# 4_SurvBot_RCU_Bluetooth.net
KiCad netlist of a schematic drawn in Altium Designer
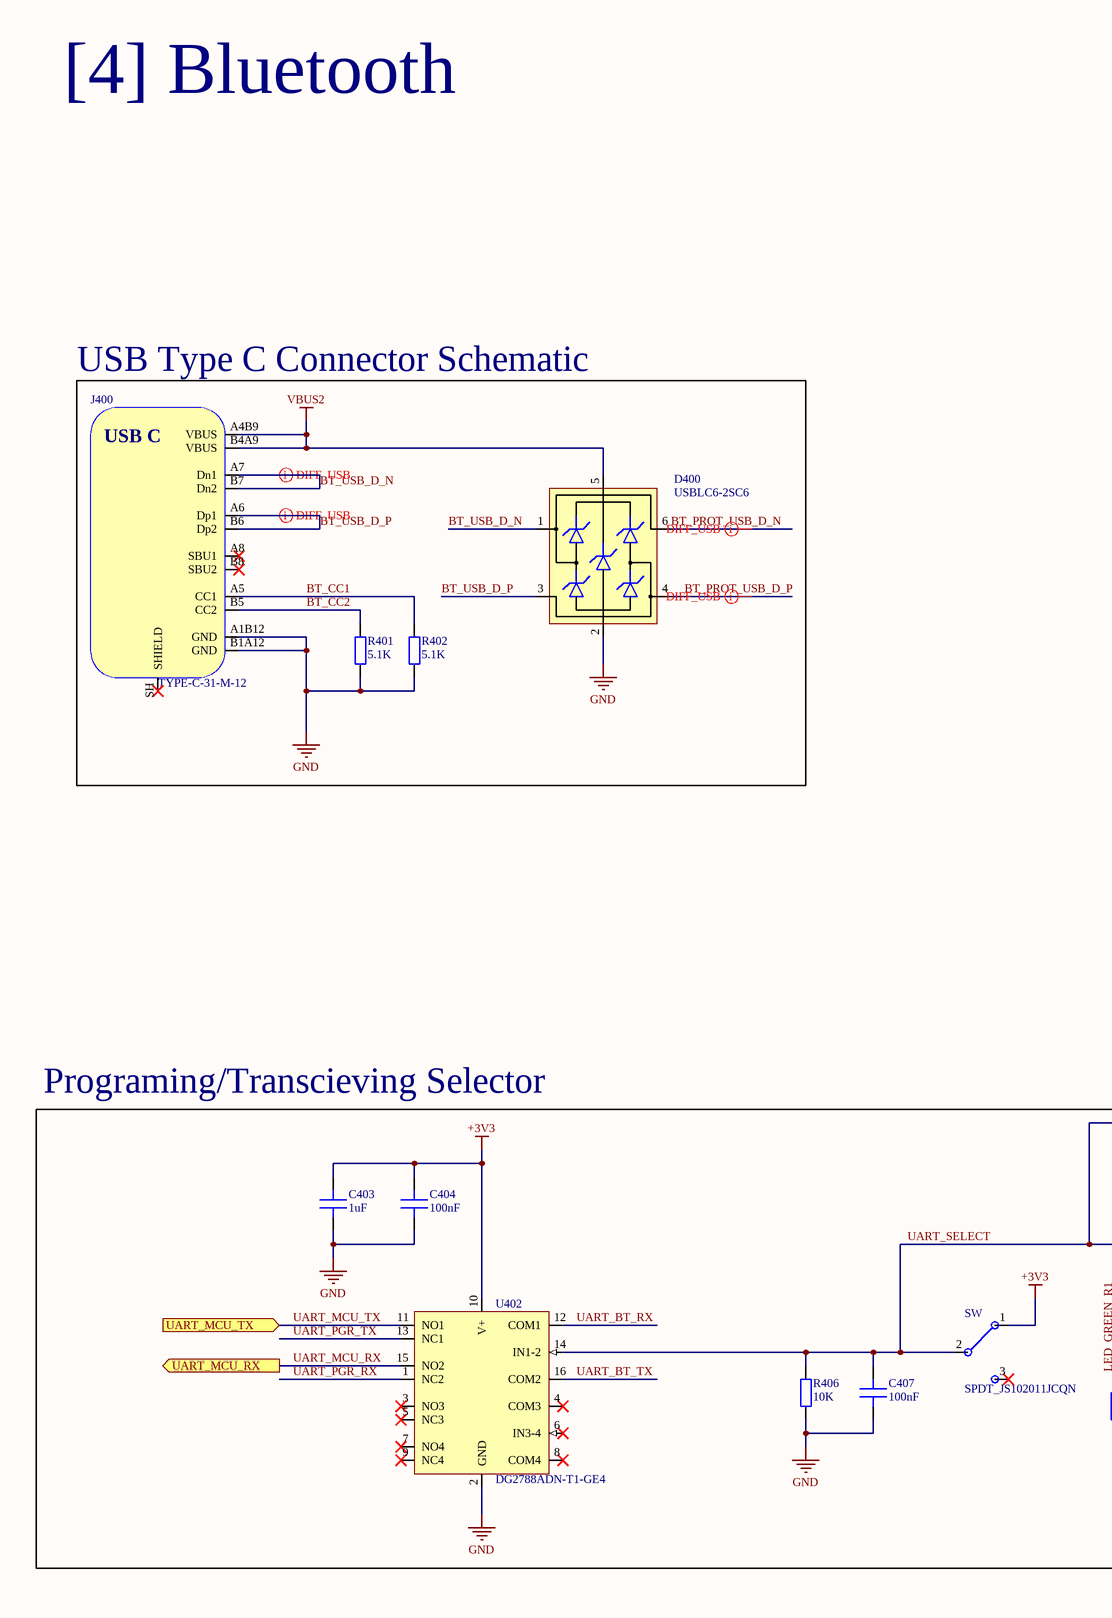
[diagram p0: 4_SurvBot_RCU_Bluetooth.SchDoc, left]
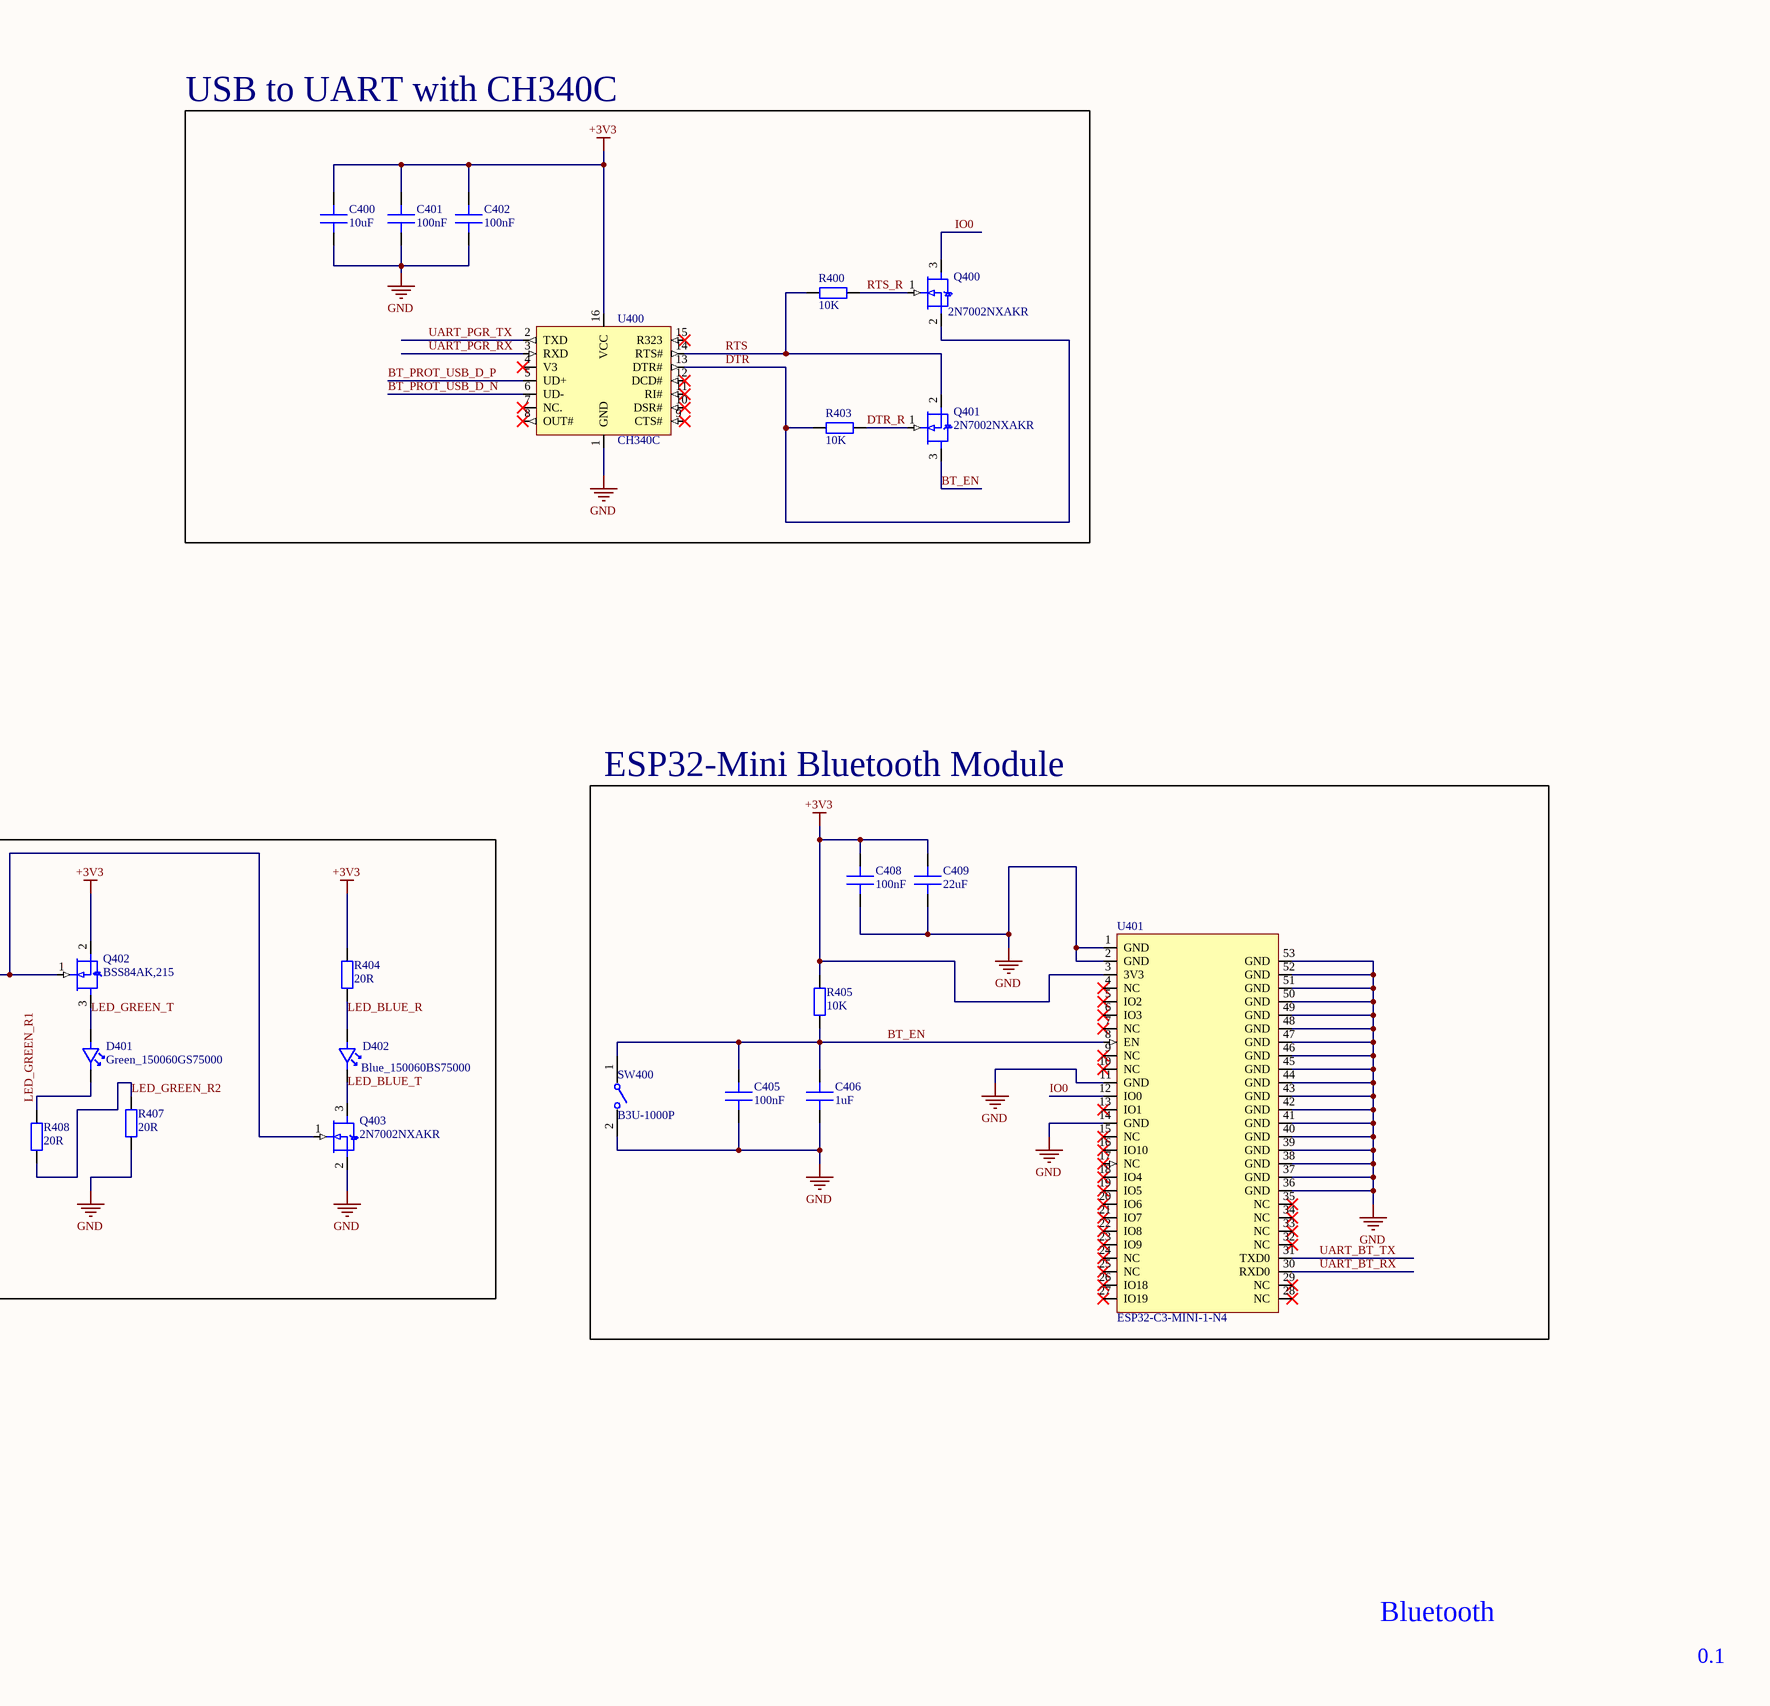
[diagram p1: 4_SurvBot_RCU_Bluetooth.SchDoc, right]

(export (version "E")
  (design (tool "Eeschema 10.0.6"))
  (components
    (comp (ref "C400")
      (value "10uF")
      (footprint "CAP_0603")
      (description "10 µF ±20% 10V Ceramic Capacitor X5R 0603 (1608 Metric)")
      (fields
        (field (name "MANUFACTURER") "Murata Electronics")
        (field (name "MANUFACTURER PART #") "GRM188R61A106ME69D")
      )
      (libsource (lib "GhaniLibrary") (part "CAP_10uF-10V-20%-0603"))
    )
    (comp (ref "C401")
      (value "100nF")
      (footprint "CAP_0603")
      (description "0.1 µF ±10% 50V Ceramic Capacitor X7R 0603 (1608 Metric)")
      (fields (field (name "MANUFACTURER") "KEMET") (field (name "MANUFACTURER PART #") "C0603C104K5RACAUTO"))
      (libsource (lib "GhaniLibrary") (part "CAP_100nF-50V-10%-0603"))
    )
    (comp (ref "C402")
      (value "100nF")
      (footprint "CAP_0603")
      (description "0.1 µF ±10% 50V Ceramic Capacitor X7R 0603 (1608 Metric)")
      (fields (field (name "MANUFACTURER") "KEMET") (field (name "MANUFACTURER PART #") "C0603C104K5RACAUTO"))
      (libsource (lib "GhaniLibrary") (part "CAP_100nF-50V-10%-0603"))
    )
    (comp (ref "C403")
      (value "1uF")
      (footprint "CAP_0603")
      (description "1 µF ±10% 16V Ceramic Capacitor X7R 0603 (1608 Metric)")
      (fields (field (name "MANUFACTURER") "YAGEO") (field (name "MANUFACTURER PART #") "CC0603KRX7R7BB105"))
      (libsource (lib "GhaniLibrary") (part "CAP_1uF-16V-10%-0603"))
    )
    (comp (ref "C404")
      (value "100nF")
      (footprint "CAP_0603")
      (description "0.1 µF ±10% 50V Ceramic Capacitor X7R 0603 (1608 Metric)")
      (fields (field (name "MANUFACTURER") "KEMET") (field (name "MANUFACTURER PART #") "C0603C104K5RACAUTO"))
      (libsource (lib "GhaniLibrary") (part "CAP_100nF-50V-10%-0603"))
    )
    (comp (ref "C405")
      (value "100nF")
      (footprint "CAP_0603")
      (description "0.1 µF ±10% 50V Ceramic Capacitor X7R 0603 (1608 Metric)")
      (fields (field (name "MANUFACTURER") "KEMET") (field (name "MANUFACTURER PART #") "C0603C104K5RACAUTO"))
      (libsource (lib "GhaniLibrary") (part "CAP_100nF-50V-10%-0603"))
    )
    (comp (ref "C406")
      (value "1uF")
      (footprint "CAP_0603")
      (description "1 µF ±10% 16V Ceramic Capacitor X7R 0603 (1608 Metric)")
      (fields (field (name "MANUFACTURER") "YAGEO") (field (name "MANUFACTURER PART #") "CC0603KRX7R7BB105"))
      (libsource (lib "GhaniLibrary") (part "CAP_1uF-16V-10%-0603"))
    )
    (comp (ref "C407")
      (value "100nF")
      (footprint "CAP_0603")
      (description "0.1 µF ±10% 50V Ceramic Capacitor X7R 0603 (1608 Metric)")
      (fields (field (name "MANUFACTURER") "KEMET") (field (name "MANUFACTURER PART #") "C0603C104K5RACAUTO"))
      (libsource (lib "GhaniLibrary") (part "CAP_100nF-50V-10%-0603"))
    )
    (comp (ref "C408")
      (value "100nF")
      (footprint "CAP_0603")
      (description "0.1 µF ±10% 50V Ceramic Capacitor X7R 0603 (1608 Metric)")
      (fields (field (name "MANUFACTURER") "KEMET") (field (name "MANUFACTURER PART #") "C0603C104K5RACAUTO"))
      (libsource (lib "GhaniLibrary") (part "CAP_100nF-50V-10%-0603"))
    )
    (comp (ref "C409")
      (value "22uF")
      (footprint "CAP_0603")
      (description "22 µF ±20% 10V Ceramic Capacitor X5R 0603 (1608 Metric)")
      (fields
        (field (name "MANUFACTURER") "Samsung Electro-Mechanics")
        (field (name "MANUFACTURER PART #") "CL10A226MP8NUNE")
      )
      (libsource (lib "GhaniLibrary") (part "CAP_22uF-10V-20%-0603"))
    )
    (comp (ref "D400")
      (value "USBLC6-2SC6")
      (footprint "SOT-23-6")
      (description "Low-Capacitance ESD Protection USB")
      (fields (field (name "MANUFACTURER") "STMicroelectronics"))
      (libsource (lib "Schematic-Lib-PhilsLab") (part "USBLC6-2SC6"))
    )
    (comp (ref "D401")
      (value "Green_150060GS75000")
      (footprint "LED_0603")
      (description "Green 520nm LED Indication - Discrete 3.2V 0603 (1608 Metric)")
      (fields
        (field (name "MANUFACTURER") "Wurth Elektronik")
        (field (name "MANUFACTURER PART #") "150060GS75000")
      )
      (libsource (lib "GhaniLibrary") (part "LED_Green-0603"))
    )
    (comp (ref "D402")
      (value "Blue_150060BS75000")
      (footprint "LED_0603")
      (description "Blue 470nm LED Indication - Discrete 3.2V 0603 (1608 Metric)")
      (fields
        (field (name "MANUFACTURER") "Wurth Elektronik")
        (field (name "MANUFACTURER PART #") "150060BS75000")
      )
      (libsource (lib "GhaniLibrary") (part "LED_Blue_0603"))
    )
    (comp (ref "J400")
      (value "TYPE-C-31-M-12")
      (footprint "USB4105-GF-A-060")
      (description "5A 1 16P Female Type-C SMD USB Connectors ROHS")
      (fields (field (name "MANUFACTURER") "Korean Hroparts Elec"))
      (libsource (lib "Schematic-Lib-PhilsLab") (part "USB4105-GF-A-060_1"))
    )
    (comp (ref "Q400")
      (value "2N7002NXAKR")
      (footprint "SOT23-3")
      (description "N-Channel 60 V 190mA (Ta), 300mA (Tc) 265mW (Ta), 1.33W (Tc) Surface Mount TO-236AB")
      (fields (field (name "MANUFACTURER") "Nexperia"))
      (libsource (lib "GhaniLibrary") (part "MOSFET-N_60V-190mA-SOT23-3"))
    )
    (comp (ref "Q401")
      (value "2N7002NXAKR")
      (footprint "SOT23-3")
      (description "N-Channel 60 V 190mA (Ta), 300mA (Tc) 265mW (Ta), 1.33W (Tc) Surface Mount TO-236AB")
      (fields (field (name "MANUFACTURER") "Nexperia"))
      (libsource (lib "GhaniLibrary") (part "MOSFET-N_60V-190mA-SOT23-3"))
    )
    (comp (ref "Q402")
      (value "BSS84AK,215")
      (footprint "SOT23-3")
      (description "P-Channel 50 V 180mA (Ta) 350mW (Ta), 1.14W (Tc) Surface Mount TO-236AB")
      (fields (field (name "MANUFACTURER") "Nexperia"))
      (libsource (lib "GhaniLibrary") (part "MOSFET-P_50V-180mA-SOT23-3"))
    )
    (comp (ref "Q403")
      (value "2N7002NXAKR")
      (footprint "SOT23-3")
      (description "N-Channel 60 V 190mA (Ta), 300mA (Tc) 265mW (Ta), 1.33W (Tc) Surface Mount TO-236AB")
      (fields (field (name "MANUFACTURER") "Nexperia"))
      (libsource (lib "GhaniLibrary") (part "MOSFET-N_60V-190mA-SOT23-3"))
    )
    (comp (ref "R400")
      (value "10K")
      (footprint "RES_0603")
      (description "10 kOhms ±1% 0.1W, 1/10W Chip Resistor 0603 (1608 Metric) Moisture Resistant Thick Film")
      (fields (field (name "MANUFACTURER") "YAGEO") (field (name "MANUFACTURER PART #") "RC0603FR-0710KL"))
      (libsource (lib "GhaniLibrary") (part "RES_10K-100mW-1%-0603"))
    )
    (comp (ref "R401")
      (value "5.1K")
      (footprint "RES_0603")
      (description "5.1 kOhms ±1% 0.1W, 1/10W Chip Resistor 0603 (1608 Metric) Moisture Resistant Thick Film")
      (fields (field (name "MANUFACTURER") "YAGEO") (field (name "MANUFACTURER PART #") "RC0603FR-075K1L"))
      (libsource (lib "GhaniLibrary") (part "RES_5.1K-100mW-1%-0603"))
    )
    (comp (ref "R402")
      (value "5.1K")
      (footprint "RES_0603")
      (description "5.1 kOhms ±1% 0.1W, 1/10W Chip Resistor 0603 (1608 Metric) Moisture Resistant Thick Film")
      (fields (field (name "MANUFACTURER") "YAGEO") (field (name "MANUFACTURER PART #") "RC0603FR-075K1L"))
      (libsource (lib "GhaniLibrary") (part "RES_5.1K-100mW-1%-0603"))
    )
    (comp (ref "R403")
      (value "10K")
      (footprint "RES_0603")
      (description "10 kOhms ±1% 0.1W, 1/10W Chip Resistor 0603 (1608 Metric) Moisture Resistant Thick Film")
      (fields (field (name "MANUFACTURER") "YAGEO") (field (name "MANUFACTURER PART #") "RC0603FR-0710KL"))
      (libsource (lib "GhaniLibrary") (part "RES_10K-100mW-1%-0603"))
    )
    (comp (ref "R404")
      (value "20R")
      (footprint "RES_0603")
      (description "20 Ohms ±1% 0.1W, 1/10W Chip Resistor 0603 (1608 Metric) Moisture Resistant Thick Film")
      (fields (field (name "MANUFACTURER") "YAGEO") (field (name "MANUFACTURER PART #") "RC0603FR-0720RL"))
      (libsource (lib "GhaniLibrary") (part "RES_20R-100mW-1%-0603"))
    )
    (comp (ref "R405")
      (value "10K")
      (footprint "RES_0603")
      (description "10 kOhms ±1% 0.1W, 1/10W Chip Resistor 0603 (1608 Metric) Moisture Resistant Thick Film")
      (fields (field (name "MANUFACTURER") "YAGEO") (field (name "MANUFACTURER PART #") "RC0603FR-0710KL"))
      (libsource (lib "GhaniLibrary") (part "RES_10K-100mW-1%-0603"))
    )
    (comp (ref "R406")
      (value "10K")
      (footprint "RES_0603")
      (description "10 kOhms ±1% 0.1W, 1/10W Chip Resistor 0603 (1608 Metric) Moisture Resistant Thick Film")
      (fields (field (name "MANUFACTURER") "YAGEO") (field (name "MANUFACTURER PART #") "RC0603FR-0710KL"))
      (libsource (lib "GhaniLibrary") (part "RES_10K-100mW-1%-0603"))
    )
    (comp (ref "R407")
      (value "20R")
      (footprint "RES_0603")
      (description "20 Ohms ±1% 0.1W, 1/10W Chip Resistor 0603 (1608 Metric) Moisture Resistant Thick Film")
      (fields (field (name "MANUFACTURER") "YAGEO") (field (name "MANUFACTURER PART #") "RC0603FR-0720RL"))
      (libsource (lib "GhaniLibrary") (part "RES_20R-100mW-1%-0603"))
    )
    (comp (ref "R408")
      (value "20R")
      (footprint "RES_0603")
      (description "20 Ohms ±1% 0.1W, 1/10W Chip Resistor 0603 (1608 Metric) Moisture Resistant Thick Film")
      (fields (field (name "MANUFACTURER") "YAGEO") (field (name "MANUFACTURER PART #") "RC0603FR-0720RL"))
      (libsource (lib "GhaniLibrary") (part "RES_20R-100mW-1%-0603"))
    )
    (comp (ref "SW")
      (value "SPDT_JS102011JCQN")
      (footprint "SPDT_Slide-JS102011JCQN")
      (description "Slide Switch SPDT Surface Mount")
      (fields (field (name "MANUFACTURER") "C&K") (field (name "MANUFACTURER PART #") "JS102011JCQN"))
      (libsource (lib "GhaniLibrary") (part "SW_SPDT_JS102011JCQN"))
    )
    (comp (ref "SW400")
      (value "B3U-1000P")
      (footprint "FP-B3U-1000P-MFG")
      (description "SWITCH TACTILE SPST-NO 0.05A 12V")
      (fields (field (name "MANUFACTURER") "Omron Electronics"))
      (libsource (lib "Altium Content Vault") (part "ae622034201233ca1abcedc05908f33"))
    )
    (comp (ref "U400")
      (value "CH340C")
      (footprint "SOP-16")
      (description "2Mbps Transceiver USB 2.0 SOP-16 USB Converters ROHS")
      (fields (field (name "MANUFACTURER") "WCH(Jiangsu Qin Heng)"))
      (libsource (lib "GhaniLibrary") (part "CH340C-SOP-16_USB_Converter"))
    )
    (comp (ref "U401")
      (value "ESP32-C3-MINI-1-N4")
      (footprint "ESP32­C3­MINI­1")
      (fields (field (name "MANUFACTURER") "Espressif Systems"))
      (libsource (lib "GhaniLibrary") (part "MCU_ESP32-C3-MINI-1-N4"))
    )
    (comp (ref "U402")
      (value "DG2788ADN-T1-GE4")
      (footprint "UQFN-16-DG2788ADN-T1-GE4")
      (description "2 Circuit IC Switch 2:1 500mOhm 16-miniQFN (1.8x2.6)")
      (fields (field (name "MANUFACTURER") "Vishay Intertech"))
      (libsource (lib "GhaniLibrary") (part "IC_DG2788ADN-T1-GE4"))
    )
  )
  (nets
    (net (code "1") (name "+3V3") (class "Default")
      (node (ref "C400") (pin "2") (pinfunction "0_2") (pintype "passive"))
      (node (ref "C401") (pin "2") (pinfunction "0_2") (pintype "passive"))
      (node (ref "C402") (pin "2") (pinfunction "0_2") (pintype "passive"))
      (node (ref "C403") (pin "2") (pinfunction "0_2") (pintype "passive"))
      (node (ref "C404") (pin "2") (pinfunction "0_2") (pintype "passive"))
      (node (ref "C408") (pin "2") (pinfunction "0_2") (pintype "passive"))
      (node (ref "C409") (pin "2") (pinfunction "0_2") (pintype "passive"))
      (node (ref "Q402") (pin "2") (pinfunction "S_2") (pintype "passive"))
      (node (ref "R404") (pin "1") (pinfunction "1_1") (pintype "passive"))
      (node (ref "R405") (pin "2") (pinfunction "2_2") (pintype "passive"))
      (node (ref "SW") (pin "1") (pintype "passive"))
      (node (ref "U400") (pin "16") (pinfunction "VCC_16") (pintype "power_in"))
      (node (ref "U401") (pin "3") (pinfunction "3V3_3") (pintype "power_in"))
      (node (ref "U402") (pin "10") (pinfunction "V+_10") (pintype "power_in"))
    )
    (net (code "2") (name "/BT_CC1") (class "Default")
      (node (ref "J400") (pin "A5") (pinfunction "CC1_A5") (pintype "passive"))
      (node (ref "R402") (pin "2") (pinfunction "2_2") (pintype "passive"))
    )
    (net (code "3") (name "/BT_CC2") (class "Default")
      (node (ref "J400") (pin "B5") (pinfunction "CC2_B5") (pintype "passive"))
      (node (ref "R401") (pin "2") (pinfunction "2_2") (pintype "passive"))
    )
    (net (code "4") (name "/BT_EN") (class "Default")
      (node (ref "C405") (pin "2") (pinfunction "0_2") (pintype "passive"))
      (node (ref "C406") (pin "2") (pinfunction "0_2") (pintype "passive"))
      (node (ref "Q401") (pin "3") (pinfunction "D_3") (pintype "passive"))
      (node (ref "R405") (pin "1") (pinfunction "1_1") (pintype "passive"))
      (node (ref "SW400") (pin "1") (pinfunction "1_1") (pintype "passive"))
      (node (ref "U401") (pin "8") (pinfunction "EN_8") (pintype "input"))
    )
    (net (code "5") (name "/BT_PROT_USB_D_N") (class "Default")
      (node (ref "D400") (pin "6") (pinfunction "IO1_6") (pintype "bidirectional"))
      (node (ref "U400") (pin "6") (pinfunction "UD-_6") (pintype "bidirectional"))
    )
    (net (code "6") (name "/BT_PROT_USB_D_P") (class "Default")
      (node (ref "D400") (pin "4") (pinfunction "IO2_4") (pintype "bidirectional"))
      (node (ref "U400") (pin "5") (pinfunction "UD+_5") (pintype "bidirectional"))
    )
    (net (code "7") (name "/BT_USB_D_N") (class "Default")
      (node (ref "D400") (pin "1") (pinfunction "IO1_1") (pintype "bidirectional"))
      (node (ref "J400") (pin "A7") (pinfunction "Dn1_A7") (pintype "passive"))
      (node (ref "J400") (pin "B7") (pinfunction "Dn2_B7") (pintype "passive"))
    )
    (net (code "8") (name "/BT_USB_D_P") (class "Default")
      (node (ref "D400") (pin "3") (pinfunction "IO2_3") (pintype "bidirectional"))
      (node (ref "J400") (pin "A6") (pinfunction "Dp1_A6") (pintype "passive"))
      (node (ref "J400") (pin "B6") (pinfunction "Dp2_B6") (pintype "passive"))
    )
    (net (code "9") (name "/DTR") (class "Default")
      (node (ref "Q400") (pin "2") (pinfunction "S_2") (pintype "passive"))
      (node (ref "R403") (pin "1") (pinfunction "1_1") (pintype "passive"))
      (node (ref "U400") (pin "13") (pinfunction "DTR#_13") (pintype "output"))
    )
    (net (code "10") (name "/DTR_R") (class "Default")
      (node (ref "Q401") (pin "1") (pinfunction "G_1") (pintype "input"))
      (node (ref "R403") (pin "2") (pinfunction "2_2") (pintype "passive"))
    )
    (net (code "11") (name "/IO0") (class "Default")
      (node (ref "Q400") (pin "3") (pinfunction "D_3") (pintype "passive"))
      (node (ref "U401") (pin "12") (pinfunction "IO0_12") (pintype "bidirectional"))
    )
    (net (code "12") (name "/LED_BLUE_R") (class "Default")
      (node (ref "D402") (pin "2") (pinfunction "2_2") (pintype "passive"))
      (node (ref "R404") (pin "2") (pinfunction "2_2") (pintype "passive"))
    )
    (net (code "13") (name "/LED_BLUE_T") (class "Default")
      (node (ref "D402") (pin "1") (pinfunction "1_1") (pintype "passive"))
      (node (ref "Q403") (pin "3") (pinfunction "D_3") (pintype "passive"))
    )
    (net (code "14") (name "/LED_GREEN_R1") (class "Default")
      (node (ref "D401") (pin "1") (pinfunction "1_1") (pintype "passive"))
      (node (ref "R408") (pin "1") (pinfunction "1_1") (pintype "passive"))
    )
    (net (code "15") (name "/LED_GREEN_R2") (class "Default")
      (node (ref "R407") (pin "2") (pinfunction "2_2") (pintype "passive"))
      (node (ref "R408") (pin "2") (pinfunction "2_2") (pintype "passive"))
    )
    (net (code "16") (name "/LED_GREEN_T") (class "Default")
      (node (ref "D401") (pin "2") (pinfunction "2_2") (pintype "passive"))
      (node (ref "Q402") (pin "3") (pinfunction "D_3") (pintype "passive"))
    )
    (net (code "17") (name "/RTS") (class "Default")
      (node (ref "Q401") (pin "2") (pinfunction "S_2") (pintype "passive"))
      (node (ref "R400") (pin "1") (pinfunction "1_1") (pintype "passive"))
      (node (ref "U400") (pin "14") (pinfunction "RTS#_14") (pintype "output"))
    )
    (net (code "18") (name "/RTS_R") (class "Default")
      (node (ref "Q400") (pin "1") (pinfunction "G_1") (pintype "input"))
      (node (ref "R400") (pin "2") (pinfunction "2_2") (pintype "passive"))
    )
    (net (code "19") (name "/UART_BT_RX") (class "Default")
      (node (ref "U401") (pin "30") (pinfunction "RXD0_30") (pintype "bidirectional"))
      (node (ref "U402") (pin "12") (pinfunction "COM1_12") (pintype "bidirectional"))
    )
    (net (code "20") (name "/UART_BT_TX") (class "Default")
      (node (ref "U401") (pin "31") (pinfunction "TXD0_31") (pintype "bidirectional"))
      (node (ref "U402") (pin "16") (pinfunction "COM2_16") (pintype "bidirectional"))
    )
    (net (code "21") (name "/UART_MCU_RX") (class "Default")
      (node (ref "U402") (pin "15") (pinfunction "NO2_15") (pintype "bidirectional"))
    )
    (net (code "22") (name "/UART_MCU_TX") (class "Default")
      (node (ref "U402") (pin "11") (pinfunction "NO1_11") (pintype "bidirectional"))
    )
    (net (code "23") (name "/UART_PGR_RX") (class "Default")
      (node (ref "U400") (pin "3") (pinfunction "RXD_3") (pintype "input"))
      (node (ref "U402") (pin "1") (pinfunction "NC2_1") (pintype "bidirectional"))
    )
    (net (code "24") (name "/UART_PGR_TX") (class "Default")
      (node (ref "U400") (pin "2") (pinfunction "TXD_2") (pintype "output"))
      (node (ref "U402") (pin "13") (pinfunction "NC1_13") (pintype "bidirectional"))
    )
    (net (code "25") (name "/UART_SELECT") (class "Default")
      (node (ref "C407") (pin "2") (pinfunction "0_2") (pintype "passive"))
      (node (ref "Q402") (pin "1") (pinfunction "G_1") (pintype "input"))
      (node (ref "Q403") (pin "1") (pinfunction "G_1") (pintype "input"))
      (node (ref "R406") (pin "2") (pinfunction "2_2") (pintype "passive"))
      (node (ref "SW") (pin "2") (pintype "passive"))
      (node (ref "U402") (pin "14") (pinfunction "IN1-2_14") (pintype "input"))
    )
    (net (code "26") (name "GND") (class "Default")
      (node (ref "C400") (pin "1") (pinfunction "0_1") (pintype "passive"))
      (node (ref "C401") (pin "1") (pinfunction "0_1") (pintype "passive"))
      (node (ref "C402") (pin "1") (pinfunction "0_1") (pintype "passive"))
      (node (ref "C403") (pin "1") (pinfunction "0_1") (pintype "passive"))
      (node (ref "C404") (pin "1") (pinfunction "0_1") (pintype "passive"))
      (node (ref "C405") (pin "1") (pinfunction "0_1") (pintype "passive"))
      (node (ref "C406") (pin "1") (pinfunction "0_1") (pintype "passive"))
      (node (ref "C407") (pin "1") (pinfunction "0_1") (pintype "passive"))
      (node (ref "C408") (pin "1") (pinfunction "0_1") (pintype "passive"))
      (node (ref "C409") (pin "1") (pinfunction "0_1") (pintype "passive"))
      (node (ref "D400") (pin "2") (pinfunction "GND_2") (pintype "power_in"))
      (node (ref "J400") (pin "A1B12") (pinfunction "GND_A1B12") (pintype "passive"))
      (node (ref "J400") (pin "B1A12") (pinfunction "GND_B1A12") (pintype "passive"))
      (node (ref "Q403") (pin "2") (pinfunction "S_2") (pintype "passive"))
      (node (ref "R401") (pin "1") (pinfunction "1_1") (pintype "passive"))
      (node (ref "R402") (pin "1") (pinfunction "1_1") (pintype "passive"))
      (node (ref "R406") (pin "1") (pinfunction "1_1") (pintype "passive"))
      (node (ref "R407") (pin "1") (pinfunction "1_1") (pintype "passive"))
      (node (ref "SW400") (pin "2") (pinfunction "2_2") (pintype "passive"))
      (node (ref "U400") (pin "1") (pinfunction "GND_1") (pintype "power_in"))
      (node (ref "U401") (pin "1") (pinfunction "GND_1") (pintype "power_in"))
      (node (ref "U401") (pin "11") (pinfunction "GND_11") (pintype "power_in"))
      (node (ref "U401") (pin "14") (pinfunction "GND_14") (pintype "power_in"))
      (node (ref "U401") (pin "2") (pinfunction "GND_2") (pintype "power_in"))
      (node (ref "U401") (pin "36") (pinfunction "GND_36") (pintype "power_in"))
      (node (ref "U401") (pin "37") (pinfunction "GND_37") (pintype "power_in"))
      (node (ref "U401") (pin "38") (pinfunction "GND_38") (pintype "power_in"))
      (node (ref "U401") (pin "39") (pinfunction "GND_39") (pintype "power_in"))
      (node (ref "U401") (pin "40") (pinfunction "GND_40") (pintype "power_in"))
      (node (ref "U401") (pin "41") (pinfunction "GND_41") (pintype "power_in"))
      (node (ref "U401") (pin "42") (pinfunction "GND_42") (pintype "power_in"))
      (node (ref "U401") (pin "43") (pinfunction "GND_43") (pintype "power_in"))
      (node (ref "U401") (pin "44") (pinfunction "GND_44") (pintype "power_in"))
      (node (ref "U401") (pin "45") (pinfunction "GND_45") (pintype "power_in"))
      (node (ref "U401") (pin "46") (pinfunction "GND_46") (pintype "power_in"))
      (node (ref "U401") (pin "47") (pinfunction "GND_47") (pintype "power_in"))
      (node (ref "U401") (pin "48") (pinfunction "GND_48") (pintype "power_in"))
      (node (ref "U401") (pin "49") (pinfunction "GND_49") (pintype "power_in"))
      (node (ref "U401") (pin "50") (pinfunction "GND_50") (pintype "power_in"))
      (node (ref "U401") (pin "51") (pinfunction "GND_51") (pintype "power_in"))
      (node (ref "U401") (pin "52") (pinfunction "GND_52") (pintype "power_in"))
      (node (ref "U401") (pin "53") (pinfunction "GND_53") (pintype "power_in"))
      (node (ref "U402") (pin "2") (pinfunction "GND_2") (pintype "power_in"))
    )
    (net (code "27") (name "VBUS2") (class "Default")
      (node (ref "D400") (pin "5") (pinfunction "VBUS_5") (pintype "power_in"))
      (node (ref "J400") (pin "A4B9") (pinfunction "VBUS_A4B9") (pintype "passive"))
      (node (ref "J400") (pin "B4A9") (pinfunction "VBUS_B4A9") (pintype "passive"))
    )
    (net (code "28") (name "unconnected-(J400-SBU1-PadA8)") (class "Default")
      (node (ref "J400") (pin "A8") (pinfunction "SBU1_A8") (pintype "passive+no_connect"))
    )
    (net (code "29") (name "unconnected-(J400-SBU2-PadB8)") (class "Default")
      (node (ref "J400") (pin "B8") (pinfunction "SBU2_B8") (pintype "passive+no_connect"))
    )
    (net (code "30") (name "unconnected-(J400-SHIELD-PadSH)") (class "Default")
      (node (ref "J400") (pin "SH") (pinfunction "SHIELD_SH") (pintype "passive+no_connect"))
    )
    (net (code "31") (name "unconnected-(SW-Pad3)") (class "Default")
      (node (ref "SW") (pin "3") (pintype "passive+no_connect"))
    )
    (net (code "32") (name "unconnected-(U400-CTS#-Pad9)") (class "Default")
      (node (ref "U400") (pin "9") (pinfunction "CTS#_9") (pintype "input+no_connect"))
    )
    (net (code "33") (name "unconnected-(U400-DCD#-Pad12)") (class "Default")
      (node (ref "U400") (pin "12") (pinfunction "DCD#_12") (pintype "input+no_connect"))
    )
    (net (code "34") (name "unconnected-(U400-DSR#-Pad10)") (class "Default")
      (node (ref "U400") (pin "10") (pinfunction "DSR#_10") (pintype "input+no_connect"))
    )
    (net (code "35") (name "unconnected-(U400-NC.-Pad7)") (class "Default")
      (node (ref "U400") (pin "7") (pinfunction "NC._7") (pintype "passive+no_connect"))
    )
    (net (code "36") (name "unconnected-(U400-OUT#-Pad8)") (class "Default")
      (node (ref "U400") (pin "8") (pinfunction "OUT#_8") (pintype "output+no_connect"))
    )
    (net (code "37") (name "unconnected-(U400-R323-Pad15)") (class "Default")
      (node (ref "U400") (pin "15") (pinfunction "R323_15") (pintype "input+no_connect"))
    )
    (net (code "38") (name "unconnected-(U400-RI#-Pad11)") (class "Default")
      (node (ref "U400") (pin "11") (pinfunction "RI#_11") (pintype "input+no_connect"))
    )
    (net (code "39") (name "unconnected-(U400-V3-Pad4)") (class "Default")
      (node (ref "U400") (pin "4") (pinfunction "V3_4") (pintype "power_in+no_connect"))
    )
    (net (code "40") (name "unconnected-(U401-IO1-Pad13)") (class "Default")
      (node (ref "U401") (pin "13") (pinfunction "IO1_13") (pintype "bidirectional+no_connect"))
    )
    (net (code "41") (name "unconnected-(U401-IO2-Pad5)") (class "Default")
      (node (ref "U401") (pin "5") (pinfunction "IO2_5") (pintype "bidirectional+no_connect"))
    )
    (net (code "42") (name "unconnected-(U401-IO3-Pad6)") (class "Default")
      (node (ref "U401") (pin "6") (pinfunction "IO3_6") (pintype "bidirectional+no_connect"))
    )
    (net (code "43") (name "unconnected-(U401-IO4-Pad18)") (class "Default")
      (node (ref "U401") (pin "18") (pinfunction "IO4_18") (pintype "bidirectional+no_connect"))
    )
    (net (code "44") (name "unconnected-(U401-IO5-Pad19)") (class "Default")
      (node (ref "U401") (pin "19") (pinfunction "IO5_19") (pintype "bidirectional+no_connect"))
    )
    (net (code "45") (name "unconnected-(U401-IO6-Pad20)") (class "Default")
      (node (ref "U401") (pin "20") (pinfunction "IO6_20") (pintype "bidirectional+no_connect"))
    )
    (net (code "46") (name "unconnected-(U401-IO7-Pad21)") (class "Default")
      (node (ref "U401") (pin "21") (pinfunction "IO7_21") (pintype "bidirectional+no_connect"))
    )
    (net (code "47") (name "unconnected-(U401-IO8-Pad22)") (class "Default")
      (node (ref "U401") (pin "22") (pinfunction "IO8_22") (pintype "bidirectional+no_connect"))
    )
    (net (code "48") (name "unconnected-(U401-IO9-Pad23)") (class "Default")
      (node (ref "U401") (pin "23") (pinfunction "IO9_23") (pintype "bidirectional+no_connect"))
    )
    (net (code "49") (name "unconnected-(U401-IO10-Pad16)") (class "Default")
      (node (ref "U401") (pin "16") (pinfunction "IO10_16") (pintype "bidirectional+no_connect"))
    )
    (net (code "50") (name "unconnected-(U401-IO18-Pad26)") (class "Default")
      (node (ref "U401") (pin "26") (pinfunction "IO18_26") (pintype "bidirectional+no_connect"))
    )
    (net (code "51") (name "unconnected-(U401-IO19-Pad27)") (class "Default")
      (node (ref "U401") (pin "27") (pinfunction "IO19_27") (pintype "bidirectional+no_connect"))
    )
    (net (code "52") (name "unconnected-(U401-NC-Pad4)") (class "Default")
      (node (ref "U401") (pin "4") (pinfunction "NC_4") (pintype "passive+no_connect"))
    )
    (net (code "53") (name "unconnected-(U401-NC-Pad7)") (class "Default")
      (node (ref "U401") (pin "7") (pinfunction "NC_7") (pintype "passive+no_connect"))
    )
    (net (code "54") (name "unconnected-(U401-NC-Pad9)") (class "Default")
      (node (ref "U401") (pin "9") (pinfunction "NC_9") (pintype "passive+no_connect"))
    )
    (net (code "55") (name "unconnected-(U401-NC-Pad10)") (class "Default")
      (node (ref "U401") (pin "10") (pinfunction "NC_10") (pintype "passive+no_connect"))
    )
    (net (code "56") (name "unconnected-(U401-NC-Pad15)") (class "Default")
      (node (ref "U401") (pin "15") (pinfunction "NC_15") (pintype "passive+no_connect"))
    )
    (net (code "57") (name "unconnected-(U401-NC-Pad17)") (class "Default")
      (node (ref "U401") (pin "17") (pinfunction "NC_17") (pintype "input+no_connect"))
    )
    (net (code "58") (name "unconnected-(U401-NC-Pad24)") (class "Default")
      (node (ref "U401") (pin "24") (pinfunction "NC_24") (pintype "passive+no_connect"))
    )
    (net (code "59") (name "unconnected-(U401-NC-Pad25)") (class "Default")
      (node (ref "U401") (pin "25") (pinfunction "NC_25") (pintype "passive+no_connect"))
    )
    (net (code "60") (name "unconnected-(U401-NC-Pad28)") (class "Default")
      (node (ref "U401") (pin "28") (pinfunction "NC_28") (pintype "passive+no_connect"))
    )
    (net (code "61") (name "unconnected-(U401-NC-Pad29)") (class "Default")
      (node (ref "U401") (pin "29") (pinfunction "NC_29") (pintype "passive+no_connect"))
    )
    (net (code "62") (name "unconnected-(U401-NC-Pad32)") (class "Default")
      (node (ref "U401") (pin "32") (pinfunction "NC_32") (pintype "passive+no_connect"))
    )
    (net (code "63") (name "unconnected-(U401-NC-Pad33)") (class "Default")
      (node (ref "U401") (pin "33") (pinfunction "NC_33") (pintype "passive+no_connect"))
    )
    (net (code "64") (name "unconnected-(U401-NC-Pad34)") (class "Default")
      (node (ref "U401") (pin "34") (pinfunction "NC_34") (pintype "passive+no_connect"))
    )
    (net (code "65") (name "unconnected-(U401-NC-Pad35)") (class "Default")
      (node (ref "U401") (pin "35") (pinfunction "NC_35") (pintype "passive+no_connect"))
    )
    (net (code "66") (name "unconnected-(U402-COM3-Pad4)") (class "Default")
      (node (ref "U402") (pin "4") (pinfunction "COM3_4") (pintype "bidirectional+no_connect"))
    )
    (net (code "67") (name "unconnected-(U402-COM4-Pad8)") (class "Default")
      (node (ref "U402") (pin "8") (pinfunction "COM4_8") (pintype "bidirectional+no_connect"))
    )
    (net (code "68") (name "unconnected-(U402-IN3-4-Pad6)") (class "Default")
      (node (ref "U402") (pin "6") (pinfunction "IN3-4_6") (pintype "input+no_connect"))
    )
    (net (code "69") (name "unconnected-(U402-NC3-Pad5)") (class "Default")
      (node (ref "U402") (pin "5") (pinfunction "NC3_5") (pintype "bidirectional+no_connect"))
    )
    (net (code "70") (name "unconnected-(U402-NC4-Pad9)") (class "Default")
      (node (ref "U402") (pin "9") (pinfunction "NC4_9") (pintype "bidirectional+no_connect"))
    )
    (net (code "71") (name "unconnected-(U402-NO3-Pad3)") (class "Default")
      (node (ref "U402") (pin "3") (pinfunction "NO3_3") (pintype "bidirectional+no_connect"))
    )
    (net (code "72") (name "unconnected-(U402-NO4-Pad7)") (class "Default")
      (node (ref "U402") (pin "7") (pinfunction "NO4_7") (pintype "bidirectional+no_connect"))
    )
  )
)
